# project.net
KiCad netlist of a schematic drawn in EAGLE
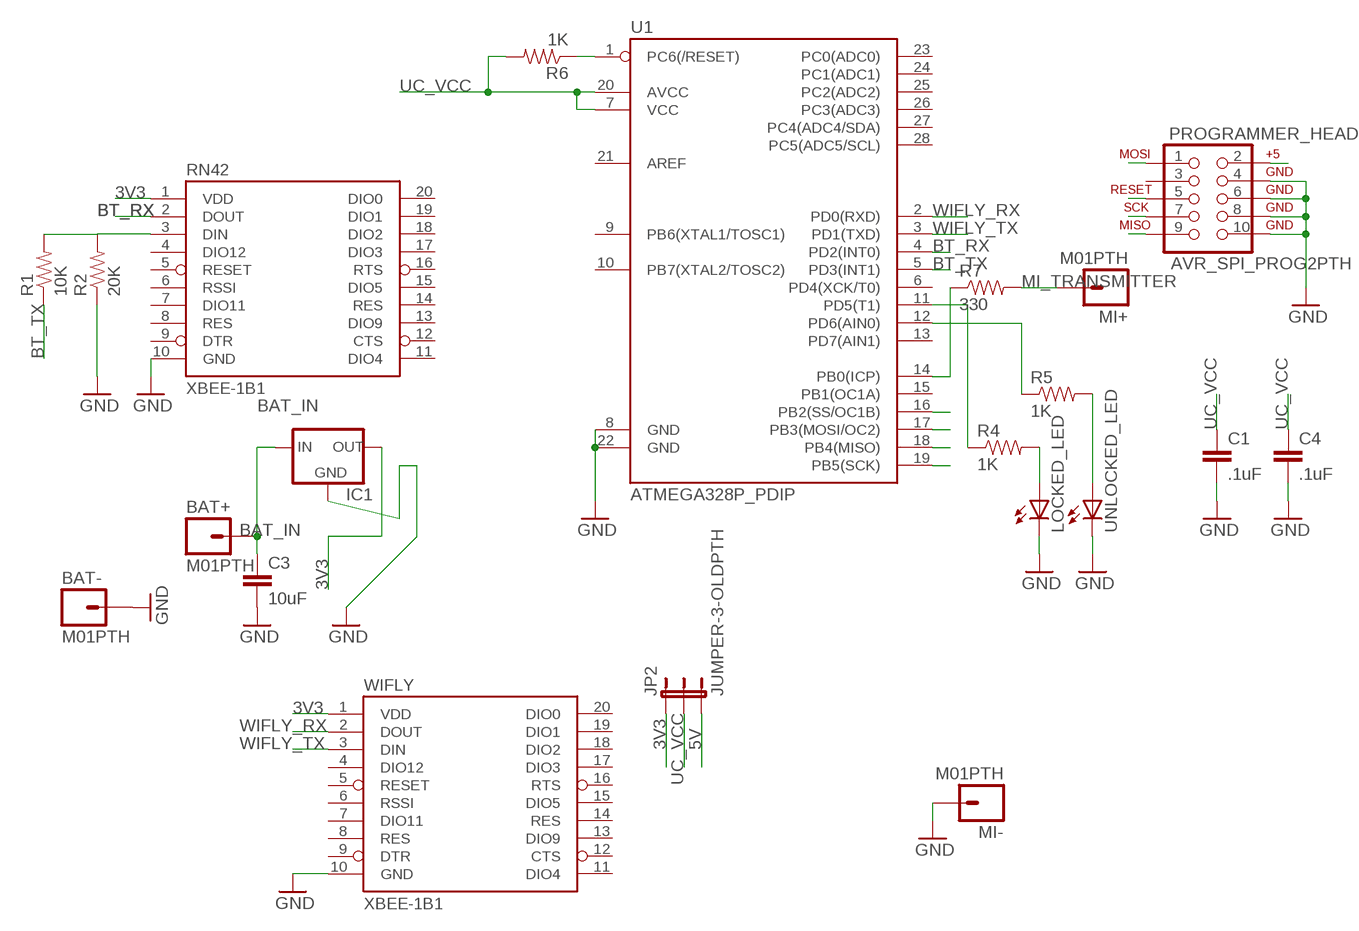
[diagram p0: schematic, sheet 1]

(export (version "E")
  (design (tool "Eeschema 10.0.6"))
  (components
    (comp (ref "BAT+")
      (value "M01PTH")
      (footprint "eagle-import:1X01")
      (libsource (lib "eagle-import") (part "M01PTH"))
    )
    (comp (ref "BAT-")
      (value "M01PTH")
      (footprint "eagle-import:1X01")
      (libsource (lib "eagle-import") (part "M01PTH"))
    )
    (comp (ref "C1")
      (value ".1uF")
      (footprint "eagle-import:CAP-PTH-SMALL")
      (libsource (lib "eagle-import") (part "CAPPTH"))
    )
    (comp (ref "C3")
      (value "10uF")
      (footprint "eagle-import:CAP-PTH-SMALL")
      (libsource (lib "eagle-import") (part "CAPPTH"))
    )
    (comp (ref "C4")
      (value ".1uF")
      (footprint "eagle-import:CAP-PTH-SMALL")
      (libsource (lib "eagle-import") (part "CAPPTH"))
    )
    (comp (ref "IC1")
      (value "V_REG_78XXSIDE")
      (footprint "eagle-import:78XXL")
      (libsource (lib "eagle-import") (part "V_REG_78XXSIDE"))
    )
    (comp (ref "JP2")
      (value "JUMPER-3-OLDPTH")
      (footprint "eagle-import:1X03")
      (libsource (lib "eagle-import") (part "JUMPER-3-OLDPTH"))
    )
    (comp (ref "LOCKED_LED")
      (value "LED5MM")
      (footprint "eagle-import:LED5MM")
      (libsource (lib "eagle-import") (part "LED5MM"))
    )
    (comp (ref "MI+")
      (value "M01PTH")
      (footprint "eagle-import:1X01")
      (libsource (lib "eagle-import") (part "M01PTH"))
    )
    (comp (ref "MI-")
      (value "M01PTH")
      (footprint "eagle-import:1X01")
      (libsource (lib "eagle-import") (part "M01PTH"))
    )
    (comp (ref "PROGRAMMER_HEADER")
      (value "AVR_SPI_PROG2PTH")
      (footprint "eagle-import:AVR_ICSP")
      (libsource (lib "eagle-import") (part "AVR_SPI_PROG2PTH"))
    )
    (comp (ref "R1")
      (value "10K")
      (footprint "eagle-import:AXIAL-0.3")
      (libsource (lib "eagle-import") (part "RESISTORAXIAL-0.3"))
    )
    (comp (ref "R2")
      (value "20K")
      (footprint "eagle-import:AXIAL-0.3")
      (libsource (lib "eagle-import") (part "RESISTORAXIAL-0.3"))
    )
    (comp (ref "R4")
      (value "1K")
      (footprint "eagle-import:AXIAL-0.3")
      (libsource (lib "eagle-import") (part "RESISTORAXIAL-0.3"))
    )
    (comp (ref "R5")
      (value "1K")
      (footprint "eagle-import:AXIAL-0.3")
      (libsource (lib "eagle-import") (part "RESISTORAXIAL-0.3"))
    )
    (comp (ref "R6")
      (value "1K")
      (footprint "eagle-import:AXIAL-0.3")
      (libsource (lib "eagle-import") (part "RESISTORAXIAL-0.3"))
    )
    (comp (ref "R7")
      (value "330")
      (footprint "eagle-import:AXIAL-0.3")
      (libsource (lib "eagle-import") (part "RESISTORAXIAL-0.3"))
    )
    (comp (ref "RN42")
      (value "XBEE-1B1")
      (footprint "eagle-import:XBEE-1")
      (libsource (lib "eagle-import") (part "XBEE-1B1"))
    )
    (comp (ref "U1")
      (value "ATMEGA328P_PDIP")
      (footprint "eagle-import:DIL28-3")
      (libsource (lib "eagle-import") (part "ATMEGA328P_PDIP"))
    )
    (comp (ref "UNLOCKED_LED")
      (value "LED5MM")
      (footprint "eagle-import:LED5MM")
      (libsource (lib "eagle-import") (part "LED5MM"))
    )
    (comp (ref "WIFLY")
      (value "XBEE-1B1")
      (footprint "eagle-import:XBEE-1")
      (libsource (lib "eagle-import") (part "XBEE-1B1"))
    )
  )
  (nets
    (net (code "1") (name "/3V3") (class "Default")
      (node (ref "IC1") (pin "OUT") (pinfunction "OUT_OUT") (pintype "output"))
      (node (ref "JP2") (pin "1") (pinfunction "1_1") (pintype "passive"))
      (node (ref "RN42") (pin "1") (pinfunction "VDD_1") (pintype "power_in"))
      (node (ref "WIFLY") (pin "1") (pinfunction "VDD_1") (pintype "power_in"))
    )
    (net (code "2") (name "/5V") (class "Default")
      (node (ref "JP2") (pin "3") (pinfunction "3_3") (pintype "passive"))
      (node (ref "PROGRAMMER_HEADER") (pin "2") (pinfunction "2_2") (pintype "passive"))
    )
    (net (code "3") (name "/BAT_IN") (class "Default")
      (node (ref "BAT+") (pin "1") (pinfunction "1_1") (pintype "passive"))
      (node (ref "C3") (pin "1") (pinfunction "1_1") (pintype "passive"))
      (node (ref "IC1") (pin "IN") (pinfunction "IN_IN") (pintype "input"))
    )
    (net (code "4") (name "/BT_RX") (class "Default")
      (node (ref "RN42") (pin "2") (pinfunction "DOUT_2") (pintype "output"))
      (node (ref "U1") (pin "4") (pinfunction "PD2(INT0)_4") (pintype "bidirectional"))
    )
    (net (code "5") (name "/BT_TX") (class "Default")
      (node (ref "R1") (pin "P$1") (pinfunction "1_P$1") (pintype "passive"))
      (node (ref "U1") (pin "5") (pinfunction "PD3(INT1)_5") (pintype "bidirectional"))
    )
    (net (code "6") (name "/MISO") (class "Default")
      (node (ref "PROGRAMMER_HEADER") (pin "9") (pinfunction "9_9") (pintype "passive"))
      (node (ref "U1") (pin "18") (pinfunction "PB4(MISO)_18") (pintype "bidirectional"))
    )
    (net (code "7") (name "/MI_TRANSMITTER") (class "Default")
      (node (ref "MI+") (pin "1") (pinfunction "1_1") (pintype "passive"))
      (node (ref "R7") (pin "P$2") (pinfunction "2_P$2") (pintype "passive"))
    )
    (net (code "8") (name "/MOSI") (class "Default")
      (node (ref "PROGRAMMER_HEADER") (pin "1") (pinfunction "1_1") (pintype "passive"))
      (node (ref "U1") (pin "17") (pinfunction "PB3(MOSI/OC2)_17") (pintype "bidirectional"))
    )
    (net (code "9") (name "/RESET") (class "Default")
      (node (ref "PROGRAMMER_HEADER") (pin "5") (pinfunction "5_5") (pintype "passive"))
      (node (ref "R6") (pin "P$1") (pinfunction "1_P$1") (pintype "passive"))
      (node (ref "U1") (pin "1") (pinfunction "PC6(/RESET)_1") (pintype "bidirectional"))
    )
    (net (code "10") (name "/SCK") (class "Default")
      (node (ref "PROGRAMMER_HEADER") (pin "7") (pinfunction "7_7") (pintype "passive"))
      (node (ref "U1") (pin "19") (pinfunction "PB5(SCK)_19") (pintype "bidirectional"))
    )
    (net (code "11") (name "/UC_VCC") (class "Default")
      (node (ref "C1") (pin "1") (pinfunction "1_1") (pintype "passive"))
      (node (ref "C4") (pin "1") (pinfunction "1_1") (pintype "passive"))
      (node (ref "JP2") (pin "2") (pinfunction "2_2") (pintype "passive"))
      (node (ref "R6") (pin "P$2") (pinfunction "2_P$2") (pintype "passive"))
      (node (ref "U1") (pin "20") (pinfunction "AVCC_20") (pintype "bidirectional"))
      (node (ref "U1") (pin "7") (pinfunction "VCC_7") (pintype "bidirectional"))
    )
    (net (code "12") (name "/WIFLY_RX") (class "Default")
      (node (ref "U1") (pin "2") (pinfunction "PD0(RXD)_2") (pintype "bidirectional"))
      (node (ref "WIFLY") (pin "2") (pinfunction "DOUT_2") (pintype "output"))
    )
    (net (code "13") (name "/WIFLY_TX") (class "Default")
      (node (ref "U1") (pin "3") (pinfunction "PD1(TXD)_3") (pintype "bidirectional"))
      (node (ref "WIFLY") (pin "3") (pinfunction "DIN_3") (pintype "input"))
    )
    (net (code "14") (name "GND") (class "Default")
      (node (ref "BAT-") (pin "1") (pinfunction "1_1") (pintype "passive"))
      (node (ref "C1") (pin "2") (pinfunction "2_2") (pintype "passive"))
      (node (ref "C3") (pin "2") (pinfunction "2_2") (pintype "passive"))
      (node (ref "C4") (pin "2") (pinfunction "2_2") (pintype "passive"))
      (node (ref "IC1") (pin "GND") (pinfunction "GND_GND") (pintype "input"))
      (node (ref "LOCKED_LED") (pin "K") (pinfunction "C_K") (pintype "passive"))
      (node (ref "MI-") (pin "1") (pinfunction "1_1") (pintype "passive"))
      (node (ref "PROGRAMMER_HEADER") (pin "10") (pinfunction "10_10") (pintype "passive"))
      (node (ref "PROGRAMMER_HEADER") (pin "4") (pinfunction "4_4") (pintype "passive"))
      (node (ref "PROGRAMMER_HEADER") (pin "6") (pinfunction "6_6") (pintype "passive"))
      (node (ref "PROGRAMMER_HEADER") (pin "8") (pinfunction "8_8") (pintype "passive"))
      (node (ref "R2") (pin "P$1") (pinfunction "1_P$1") (pintype "passive"))
      (node (ref "RN42") (pin "10") (pinfunction "GND_10") (pintype "power_in"))
      (node (ref "U1") (pin "22") (pinfunction "GND_22") (pintype "bidirectional"))
      (node (ref "U1") (pin "8") (pinfunction "GND_8") (pintype "bidirectional"))
      (node (ref "UNLOCKED_LED") (pin "K") (pinfunction "C_K") (pintype "passive"))
      (node (ref "WIFLY") (pin "10") (pinfunction "GND_10") (pintype "power_in"))
    )
    (net (code "15") (name "Net-(R1-2)") (class "Default")
      (node (ref "R1") (pin "P$2") (pinfunction "2_P$2") (pintype "passive"))
      (node (ref "R2") (pin "P$2") (pinfunction "2_P$2") (pintype "passive"))
      (node (ref "RN42") (pin "3") (pinfunction "DIN_3") (pintype "input"))
    )
    (net (code "16") (name "Net-(R4-1)") (class "Default")
      (node (ref "R4") (pin "P$1") (pinfunction "1_P$1") (pintype "passive"))
      (node (ref "U1") (pin "11") (pinfunction "PD5(T1)_11") (pintype "bidirectional"))
    )
    (net (code "17") (name "Net-(R4-2)") (class "Default")
      (node (ref "LOCKED_LED") (pin "A") (pinfunction "A_A") (pintype "passive"))
      (node (ref "R4") (pin "P$2") (pinfunction "2_P$2") (pintype "passive"))
    )
    (net (code "18") (name "Net-(R5-1)") (class "Default")
      (node (ref "R5") (pin "P$1") (pinfunction "1_P$1") (pintype "passive"))
      (node (ref "U1") (pin "12") (pinfunction "PD6(AIN0)_12") (pintype "bidirectional"))
    )
    (net (code "19") (name "Net-(R5-2)") (class "Default")
      (node (ref "R5") (pin "P$2") (pinfunction "2_P$2") (pintype "passive"))
      (node (ref "UNLOCKED_LED") (pin "A") (pinfunction "A_A") (pintype "passive"))
    )
    (net (code "20") (name "Net-(R7-1)") (class "Default")
      (node (ref "R7") (pin "P$1") (pinfunction "1_P$1") (pintype "passive"))
      (node (ref "U1") (pin "14") (pinfunction "PB0(ICP)_14") (pintype "bidirectional"))
    )
    (net (code "21") (name "unconnected-(PROGRAMMER_HEADER-Pad3)") (class "Default")
      (node (ref "PROGRAMMER_HEADER") (pin "3") (pinfunction "3_3") (pintype "passive"))
    )
    (net (code "22") (name "unconnected-(RN42-CTS-Pad12)") (class "Default")
      (node (ref "RN42") (pin "12") (pinfunction "CTS_12") (pintype "output"))
    )
    (net (code "23") (name "unconnected-(RN42-DIO0-Pad20)") (class "Default")
      (node (ref "RN42") (pin "20") (pinfunction "DIO0_20") (pintype "bidirectional"))
    )
    (net (code "24") (name "unconnected-(RN42-DIO1-Pad19)") (class "Default")
      (node (ref "RN42") (pin "19") (pinfunction "DIO1_19") (pintype "bidirectional"))
    )
    (net (code "25") (name "unconnected-(RN42-DIO2-Pad18)") (class "Default")
      (node (ref "RN42") (pin "18") (pinfunction "DIO2_18") (pintype "bidirectional"))
    )
    (net (code "26") (name "unconnected-(RN42-DIO3-Pad17)") (class "Default")
      (node (ref "RN42") (pin "17") (pinfunction "DIO3_17") (pintype "bidirectional"))
    )
    (net (code "27") (name "unconnected-(RN42-DIO4-Pad11)") (class "Default")
      (node (ref "RN42") (pin "11") (pinfunction "DIO4_11") (pintype "bidirectional"))
    )
    (net (code "28") (name "unconnected-(RN42-DIO5-Pad15)") (class "Default")
      (node (ref "RN42") (pin "15") (pinfunction "DIO5_15") (pintype "bidirectional"))
    )
    (net (code "29") (name "unconnected-(RN42-DIO9-Pad13)") (class "Default")
      (node (ref "RN42") (pin "13") (pinfunction "DIO9_13") (pintype "bidirectional"))
    )
    (net (code "30") (name "unconnected-(RN42-DIO11-Pad7)") (class "Default")
      (node (ref "RN42") (pin "7") (pinfunction "DIO11_7") (pintype "bidirectional"))
    )
    (net (code "31") (name "unconnected-(RN42-DIO12-Pad4)") (class "Default")
      (node (ref "RN42") (pin "4") (pinfunction "DIO12_4") (pintype "bidirectional"))
    )
    (net (code "32") (name "unconnected-(RN42-DTR-Pad9)") (class "Default")
      (node (ref "RN42") (pin "9") (pinfunction "DTR_9") (pintype "bidirectional"))
    )
    (net (code "33") (name "unconnected-(RN42-RES-Pad8)") (class "Default")
      (node (ref "RN42") (pin "8") (pinfunction "RES_8") (pintype "bidirectional"))
    )
    (net (code "34") (name "unconnected-(RN42-RES-Pad14)") (class "Default")
      (node (ref "RN42") (pin "14") (pinfunction "RES_14") (pintype "bidirectional"))
    )
    (net (code "35") (name "unconnected-(RN42-RESET-Pad5)") (class "Default")
      (node (ref "RN42") (pin "5") (pinfunction "RESET_5") (pintype "input"))
    )
    (net (code "36") (name "unconnected-(RN42-RSSI-Pad6)") (class "Default")
      (node (ref "RN42") (pin "6") (pinfunction "RSSI_6") (pintype "bidirectional"))
    )
    (net (code "37") (name "unconnected-(RN42-RTS-Pad16)") (class "Default")
      (node (ref "RN42") (pin "16") (pinfunction "RTS_16") (pintype "input"))
    )
    (net (code "38") (name "unconnected-(U1-AREF-Pad21)") (class "Default")
      (node (ref "U1") (pin "21") (pinfunction "AREF_21") (pintype "bidirectional"))
    )
    (net (code "39") (name "unconnected-(U1-PB1(OC1A)-Pad15)") (class "Default")
      (node (ref "U1") (pin "15") (pinfunction "PB1(OC1A)_15") (pintype "bidirectional"))
    )
    (net (code "40") (name "unconnected-(U1-PB2(SS{slash}OC1B)-Pad16)") (class "Default")
      (node (ref "U1") (pin "16") (pinfunction "PB2(SS/OC1B)_16") (pintype "bidirectional"))
    )
    (net (code "41") (name "unconnected-(U1-PB6(XTAL1{slash}TOSC1)-Pad9)") (class "Default")
      (node (ref "U1") (pin "9") (pinfunction "PB6(XTAL1/TOSC1)_9") (pintype "bidirectional"))
    )
    (net (code "42") (name "unconnected-(U1-PB7(XTAL2{slash}TOSC2)-Pad10)") (class "Default")
      (node (ref "U1") (pin "10") (pinfunction "PB7(XTAL2/TOSC2)_10") (pintype "bidirectional"))
    )
    (net (code "43") (name "unconnected-(U1-PC0(ADC0)-Pad23)") (class "Default")
      (node (ref "U1") (pin "23") (pinfunction "PC0(ADC0)_23") (pintype "bidirectional"))
    )
    (net (code "44") (name "unconnected-(U1-PC1(ADC1)-Pad24)") (class "Default")
      (node (ref "U1") (pin "24") (pinfunction "PC1(ADC1)_24") (pintype "bidirectional"))
    )
    (net (code "45") (name "unconnected-(U1-PC2(ADC2)-Pad25)") (class "Default")
      (node (ref "U1") (pin "25") (pinfunction "PC2(ADC2)_25") (pintype "bidirectional"))
    )
    (net (code "46") (name "unconnected-(U1-PC3(ADC3)-Pad26)") (class "Default")
      (node (ref "U1") (pin "26") (pinfunction "PC3(ADC3)_26") (pintype "bidirectional"))
    )
    (net (code "47") (name "unconnected-(U1-PC4(ADC4{slash}SDA)-Pad27)") (class "Default")
      (node (ref "U1") (pin "27") (pinfunction "PC4(ADC4/SDA)_27") (pintype "bidirectional"))
    )
    (net (code "48") (name "unconnected-(U1-PC5(ADC5{slash}SCL)-Pad28)") (class "Default")
      (node (ref "U1") (pin "28") (pinfunction "PC5(ADC5/SCL)_28") (pintype "bidirectional"))
    )
    (net (code "49") (name "unconnected-(U1-PD4(XCK{slash}T0)-Pad6)") (class "Default")
      (node (ref "U1") (pin "6") (pinfunction "PD4(XCK/T0)_6") (pintype "bidirectional"))
    )
    (net (code "50") (name "unconnected-(U1-PD7(AIN1)-Pad13)") (class "Default")
      (node (ref "U1") (pin "13") (pinfunction "PD7(AIN1)_13") (pintype "bidirectional"))
    )
    (net (code "51") (name "unconnected-(WIFLY-CTS-Pad12)") (class "Default")
      (node (ref "WIFLY") (pin "12") (pinfunction "CTS_12") (pintype "output"))
    )
    (net (code "52") (name "unconnected-(WIFLY-DIO0-Pad20)") (class "Default")
      (node (ref "WIFLY") (pin "20") (pinfunction "DIO0_20") (pintype "bidirectional"))
    )
    (net (code "53") (name "unconnected-(WIFLY-DIO1-Pad19)") (class "Default")
      (node (ref "WIFLY") (pin "19") (pinfunction "DIO1_19") (pintype "bidirectional"))
    )
    (net (code "54") (name "unconnected-(WIFLY-DIO2-Pad18)") (class "Default")
      (node (ref "WIFLY") (pin "18") (pinfunction "DIO2_18") (pintype "bidirectional"))
    )
    (net (code "55") (name "unconnected-(WIFLY-DIO3-Pad17)") (class "Default")
      (node (ref "WIFLY") (pin "17") (pinfunction "DIO3_17") (pintype "bidirectional"))
    )
    (net (code "56") (name "unconnected-(WIFLY-DIO4-Pad11)") (class "Default")
      (node (ref "WIFLY") (pin "11") (pinfunction "DIO4_11") (pintype "bidirectional"))
    )
    (net (code "57") (name "unconnected-(WIFLY-DIO5-Pad15)") (class "Default")
      (node (ref "WIFLY") (pin "15") (pinfunction "DIO5_15") (pintype "bidirectional"))
    )
    (net (code "58") (name "unconnected-(WIFLY-DIO9-Pad13)") (class "Default")
      (node (ref "WIFLY") (pin "13") (pinfunction "DIO9_13") (pintype "bidirectional"))
    )
    (net (code "59") (name "unconnected-(WIFLY-DIO11-Pad7)") (class "Default")
      (node (ref "WIFLY") (pin "7") (pinfunction "DIO11_7") (pintype "bidirectional"))
    )
    (net (code "60") (name "unconnected-(WIFLY-DIO12-Pad4)") (class "Default")
      (node (ref "WIFLY") (pin "4") (pinfunction "DIO12_4") (pintype "bidirectional"))
    )
    (net (code "61") (name "unconnected-(WIFLY-DTR-Pad9)") (class "Default")
      (node (ref "WIFLY") (pin "9") (pinfunction "DTR_9") (pintype "bidirectional"))
    )
    (net (code "62") (name "unconnected-(WIFLY-RES-Pad8)") (class "Default")
      (node (ref "WIFLY") (pin "8") (pinfunction "RES_8") (pintype "bidirectional"))
    )
    (net (code "63") (name "unconnected-(WIFLY-RES-Pad14)") (class "Default")
      (node (ref "WIFLY") (pin "14") (pinfunction "RES_14") (pintype "bidirectional"))
    )
    (net (code "64") (name "unconnected-(WIFLY-RESET-Pad5)") (class "Default")
      (node (ref "WIFLY") (pin "5") (pinfunction "RESET_5") (pintype "input"))
    )
    (net (code "65") (name "unconnected-(WIFLY-RSSI-Pad6)") (class "Default")
      (node (ref "WIFLY") (pin "6") (pinfunction "RSSI_6") (pintype "bidirectional"))
    )
    (net (code "66") (name "unconnected-(WIFLY-RTS-Pad16)") (class "Default")
      (node (ref "WIFLY") (pin "16") (pinfunction "RTS_16") (pintype "input"))
    )
  )
)
